# MAX30105_Breakout.net
KiCad netlist of a schematic drawn in EAGLE
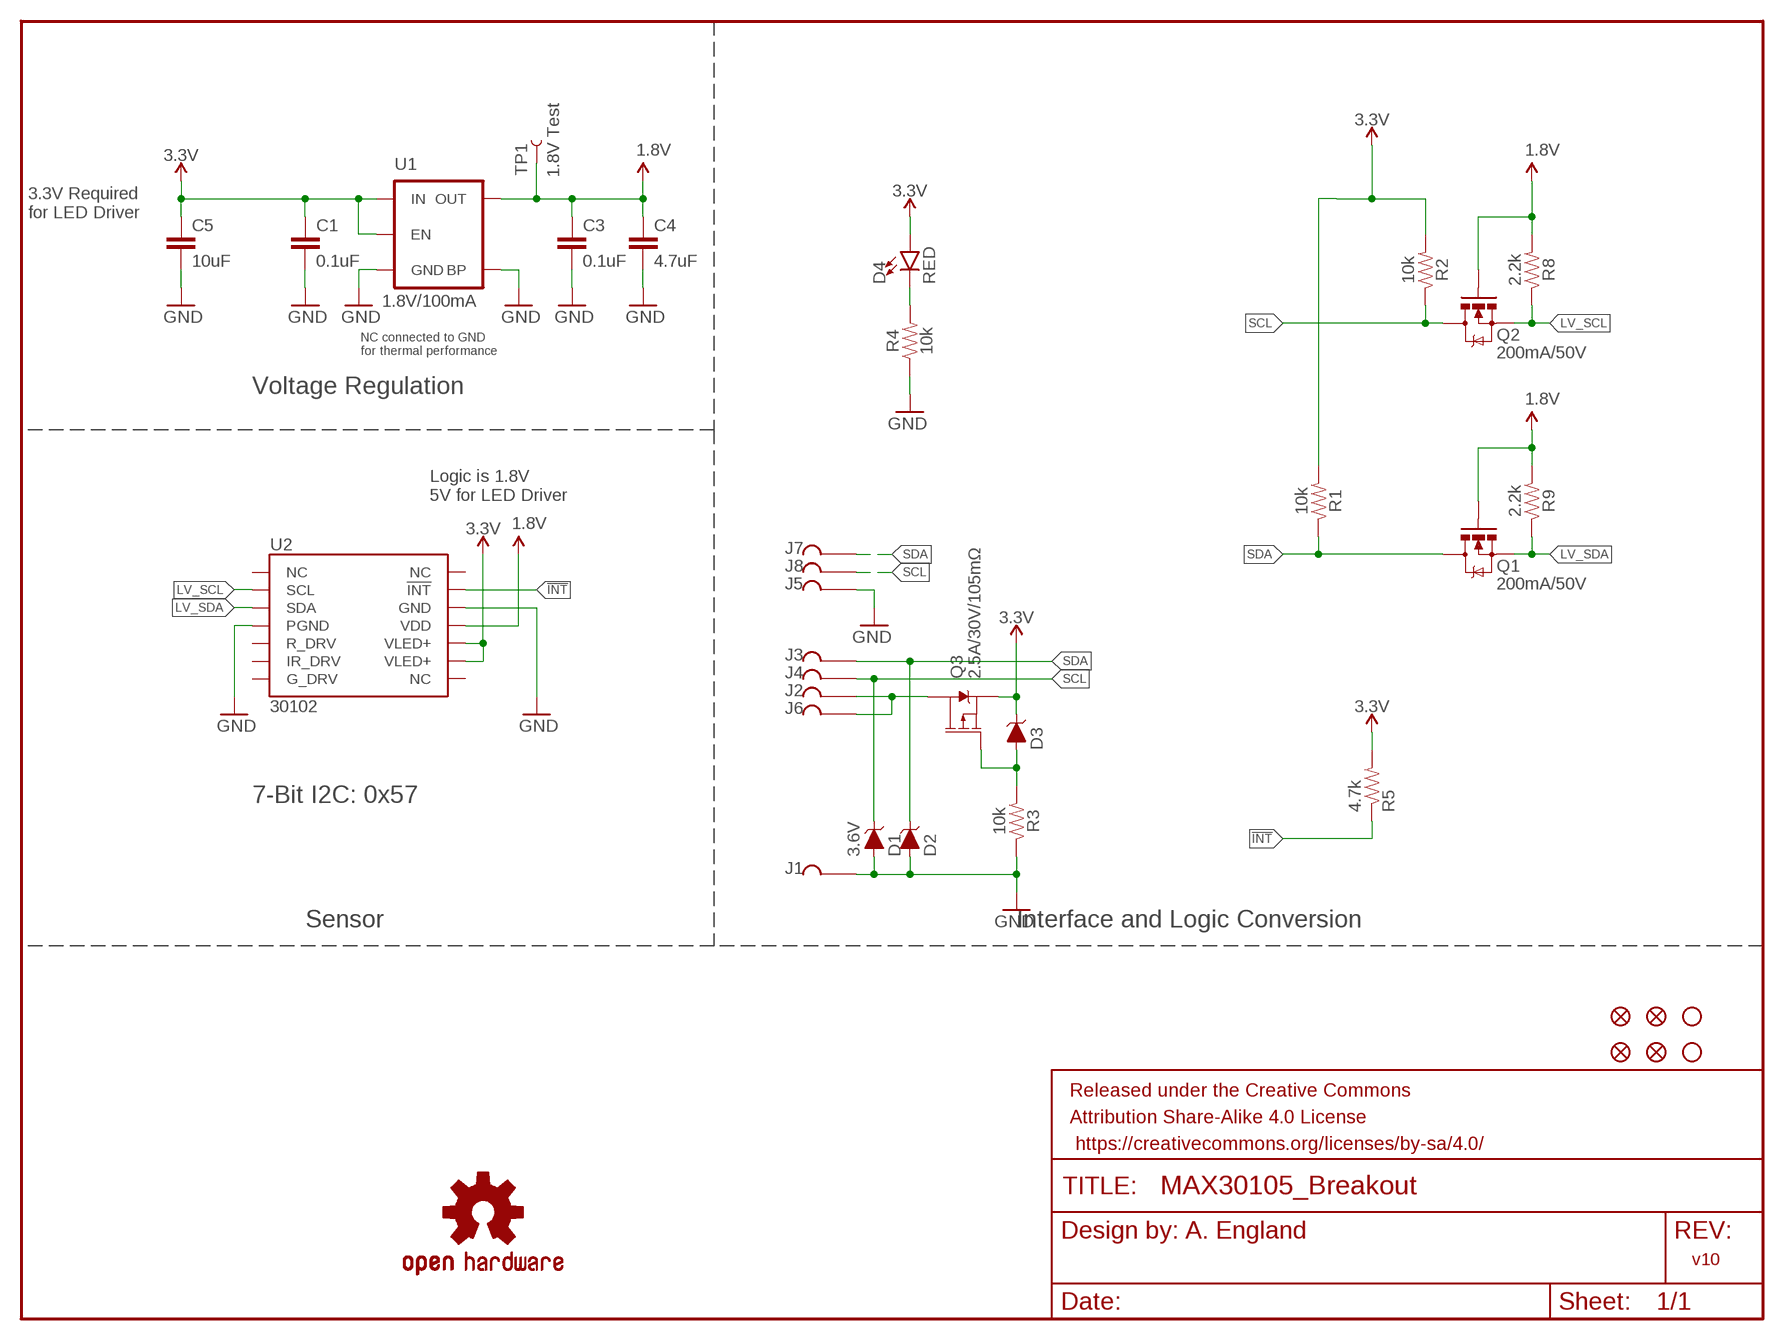
[diagram p0: schematic, sheet 1]

(export (version "E")
  (design (tool "Eeschema 10.0.6"))
  (components
    (comp (ref "C1")
      (value "0.1uF")
      (footprint "eagle-import:0603")
      (libsource (lib "eagle-import") (part "0.1UF-0603-25V-(+80/-20%)"))
    )
    (comp (ref "C3")
      (value "0.1uF")
      (footprint "eagle-import:0603")
      (libsource (lib "eagle-import") (part "0.1UF-0603-25V-(+80/-20%)"))
    )
    (comp (ref "C4")
      (value "4.7uF")
      (footprint "eagle-import:0603")
      (libsource (lib "eagle-import") (part "4.7UF-0603-6.3V-(10%)"))
    )
    (comp (ref "C5")
      (value "10uF")
      (footprint "eagle-import:0603")
      (libsource (lib "eagle-import") (part "10UF-0603-6.3V-20%"))
    )
    (comp (ref "D1")
      (value "3.6V")
      (footprint "eagle-import:SOD-323")
      (libsource (lib "eagle-import") (part "DIODE-ZENER-BZT52C3V6S"))
    )
    (comp (ref "D2")
      (value "3.6V")
      (footprint "eagle-import:SOD-323")
      (libsource (lib "eagle-import") (part "DIODE-ZENER-BZT52C3V6S"))
    )
    (comp (ref "D3")
      (value "3.6V")
      (footprint "eagle-import:SOD-323")
      (libsource (lib "eagle-import") (part "DIODE-ZENER-BZT52C3V6S"))
    )
    (comp (ref "D4")
      (value "RED")
      (footprint "eagle-import:LED-0603")
      (libsource (lib "eagle-import") (part "LED-RED0603"))
    )
    (comp (ref "FID1")
      (value "FIDUCIALUFIDUCIAL")
      (footprint "eagle-import:FIDUCIAL-MICRO")
      (libsource (lib "eagle-import") (part "FIDUCIALUFIDUCIAL"))
    )
    (comp (ref "FID2")
      (value "FIDUCIALUFIDUCIAL")
      (footprint "eagle-import:FIDUCIAL-MICRO")
      (libsource (lib "eagle-import") (part "FIDUCIALUFIDUCIAL"))
    )
    (comp (ref "FID3")
      (value "FIDUCIALUFIDUCIAL")
      (footprint "eagle-import:FIDUCIAL-MICRO")
      (libsource (lib "eagle-import") (part "FIDUCIALUFIDUCIAL"))
    )
    (comp (ref "FID4")
      (value "FIDUCIALUFIDUCIAL")
      (footprint "eagle-import:FIDUCIAL-MICRO")
      (libsource (lib "eagle-import") (part "FIDUCIALUFIDUCIAL"))
    )
    (comp (ref "FRAME1")
      (value "FRAME-LETTER")
      (footprint "eagle-import:CREATIVE_COMMONS")
      (libsource (lib "eagle-import") (part "FRAME-LETTER"))
    )
    (comp (ref "J1")
      (value "GATORGATOR_MINI")
      (footprint "eagle-import:GATOR_MINI")
      (libsource (lib "eagle-import") (part "GATORGATOR_MINI"))
    )
    (comp (ref "J2")
      (value "GATORGATOR_MINI")
      (footprint "eagle-import:GATOR_MINI")
      (libsource (lib "eagle-import") (part "GATORGATOR_MINI"))
    )
    (comp (ref "J3")
      (value "GATORGATOR_MINI")
      (footprint "eagle-import:GATOR_MINI")
      (libsource (lib "eagle-import") (part "GATORGATOR_MINI"))
    )
    (comp (ref "J4")
      (value "GATORGATOR_MINI")
      (footprint "eagle-import:GATOR_MINI")
      (libsource (lib "eagle-import") (part "GATORGATOR_MINI"))
    )
    (comp (ref "J5")
      (value "GATORGATOR_MINI")
      (footprint "eagle-import:GATOR_MINI")
      (libsource (lib "eagle-import") (part "GATORGATOR_MINI"))
    )
    (comp (ref "J6")
      (value "GATORGATOR_MINI")
      (footprint "eagle-import:GATOR_MINI")
      (libsource (lib "eagle-import") (part "GATORGATOR_MINI"))
    )
    (comp (ref "J7")
      (value "GATORGATOR_MINI")
      (footprint "eagle-import:GATOR_MINI")
      (libsource (lib "eagle-import") (part "GATORGATOR_MINI"))
    )
    (comp (ref "J8")
      (value "GATORGATOR_MINI")
      (footprint "eagle-import:GATOR_MINI")
      (libsource (lib "eagle-import") (part "GATORGATOR_MINI"))
    )
    (comp (ref "LOGO2")
      (value "OSHW-LOGOS")
      (footprint "eagle-import:OSHW-LOGO-S")
      (libsource (lib "eagle-import") (part "OSHW-LOGOS"))
    )
    (comp (ref "Q1")
      (value "200mA/50V")
      (footprint "eagle-import:SOT23-3@1")
      (libsource (lib "eagle-import") (part "MOSFET-NCHANNELBSS138"))
    )
    (comp (ref "Q2")
      (value "200mA/50V")
      (footprint "eagle-import:SOT23-3@1")
      (libsource (lib "eagle-import") (part "MOSFET-NCHANNELBSS138"))
    )
    (comp (ref "Q3")
      (value "2.5A/30V/105mΩ")
      (footprint "eagle-import:SOT23-3")
      (libsource (lib "eagle-import") (part "MOSFET_PCH-DMG2307L"))
    )
    (comp (ref "R1")
      (value "10k")
      (footprint "eagle-import:0603")
      (libsource (lib "eagle-import") (part "10KOHM-0603-1/10W-1%"))
    )
    (comp (ref "R2")
      (value "10k")
      (footprint "eagle-import:0603")
      (libsource (lib "eagle-import") (part "10KOHM-0603-1/10W-1%"))
    )
    (comp (ref "R3")
      (value "10k")
      (footprint "eagle-import:0603")
      (libsource (lib "eagle-import") (part "10KOHM-0603-1/10W-1%"))
    )
    (comp (ref "R4")
      (value "10k")
      (footprint "eagle-import:0603")
      (libsource (lib "eagle-import") (part "10KOHM-0603-1/10W-1%"))
    )
    (comp (ref "R5")
      (value "4.7k")
      (footprint "eagle-import:0603")
      (libsource (lib "eagle-import") (part "4.7KOHM-0603-1/10W-1%"))
    )
    (comp (ref "R8")
      (value "2.2k")
      (footprint "eagle-import:0603")
      (libsource (lib "eagle-import") (part "2.2KOHM-0603-1/10W-1%"))
    )
    (comp (ref "R9")
      (value "2.2k")
      (footprint "eagle-import:0603")
      (libsource (lib "eagle-import") (part "2.2KOHM-0603-1/10W-1%"))
    )
    (comp (ref "STANDOFF2")
      (value "STAND-OFF")
      (footprint "eagle-import:STAND-OFF")
      (libsource (lib "eagle-import") (part "STAND-OFF"))
    )
    (comp (ref "STANDOFF3")
      (value "STAND-OFF")
      (footprint "eagle-import:STAND-OFF")
      (libsource (lib "eagle-import") (part "STAND-OFF"))
    )
    (comp (ref "TP1")
      (value "1.8V Test")
      (footprint "eagle-import:PAD.03X.04")
      (libsource (lib "eagle-import") (part "TEST-POINT3X4"))
    )
    (comp (ref "U1")
      (value "1.8V/100mA")
      (footprint "eagle-import:SC70")
      (libsource (lib "eagle-import") (part "V_REG_SP62141.8V"))
    )
    (comp (ref "U2")
      (value "30102")
      (footprint "eagle-import:OLGA-14")
      (libsource (lib "eagle-import") (part "MAX3010X-30102"))
    )
  )
  (nets
    (net (code "1") (name "/~{INT}") (class "Default")
      (node (ref "R5") (pin "1") (pinfunction "1_1") (pintype "passive"))
      (node (ref "U2") (pin "13") (pinfunction "~{INT}_13") (pintype "bidirectional"))
    )
    (net (code "2") (name "1.8V") (class "Default")
      (node (ref "C3") (pin "1") (pinfunction "1_1") (pintype "passive"))
      (node (ref "C4") (pin "1") (pinfunction "1_1") (pintype "passive"))
      (node (ref "Q1") (pin "1") (pinfunction "G_1") (pintype "passive"))
      (node (ref "Q2") (pin "1") (pinfunction "G_1") (pintype "passive"))
      (node (ref "R8") (pin "2") (pinfunction "2_2") (pintype "passive"))
      (node (ref "R9") (pin "2") (pinfunction "2_2") (pintype "passive"))
      (node (ref "TP1") (pin "P$1") (pinfunction "1_P$1") (pintype "bidirectional"))
      (node (ref "U1") (pin "5") (pinfunction "OUT_5") (pintype "passive"))
      (node (ref "U2") (pin "11") (pinfunction "VDD_11") (pintype "bidirectional"))
    )
    (net (code "3") (name "3.3V") (class "Default")
      (node (ref "C1") (pin "1") (pinfunction "1_1") (pintype "passive"))
      (node (ref "C5") (pin "1") (pinfunction "1_1") (pintype "passive"))
      (node (ref "D3") (pin "C") (pinfunction "C_C") (pintype "passive"))
      (node (ref "D4") (pin "A") (pinfunction "A_A") (pintype "passive"))
      (node (ref "Q3") (pin "2") (pinfunction "S_2") (pintype "bidirectional"))
      (node (ref "R1") (pin "2") (pinfunction "2_2") (pintype "passive"))
      (node (ref "R2") (pin "2") (pinfunction "2_2") (pintype "passive"))
      (node (ref "R5") (pin "2") (pinfunction "2_2") (pintype "passive"))
      (node (ref "U1") (pin "1") (pinfunction "IN_1") (pintype "input"))
      (node (ref "U1") (pin "3") (pinfunction "EN_3") (pintype "input"))
      (node (ref "U2") (pin "10") (pinfunction "VLED+_10") (pintype "bidirectional"))
      (node (ref "U2") (pin "9") (pinfunction "VLED+_9") (pintype "bidirectional"))
    )
    (net (code "4") (name "GND") (class "Default")
      (node (ref "C1") (pin "2") (pinfunction "2_2") (pintype "passive"))
      (node (ref "C3") (pin "2") (pinfunction "2_2") (pintype "passive"))
      (node (ref "C4") (pin "2") (pinfunction "2_2") (pintype "passive"))
      (node (ref "C5") (pin "2") (pinfunction "2_2") (pintype "passive"))
      (node (ref "D1") (pin "A") (pinfunction "A_A") (pintype "passive"))
      (node (ref "D2") (pin "A") (pinfunction "A_A") (pintype "passive"))
      (node (ref "J1") (pin "P$2") (pinfunction "P$1_P$2") (pintype "bidirectional"))
      (node (ref "J5") (pin "P$2") (pinfunction "P$1_P$2") (pintype "bidirectional"))
      (node (ref "R3") (pin "1") (pinfunction "1_1") (pintype "passive"))
      (node (ref "R4") (pin "1") (pinfunction "1_1") (pintype "passive"))
      (node (ref "U1") (pin "2") (pinfunction "GND_2") (pintype "input"))
      (node (ref "U1") (pin "4") (pinfunction "BP_4") (pintype "input"))
      (node (ref "U2") (pin "12") (pinfunction "GND_12") (pintype "bidirectional"))
      (node (ref "U2") (pin "4") (pinfunction "PGND_4") (pintype "bidirectional"))
    )
    (net (code "5") (name "LV_SCL") (class "Default")
      (node (ref "Q2") (pin "2") (pinfunction "S_2") (pintype "passive"))
      (node (ref "R8") (pin "1") (pinfunction "1_1") (pintype "passive"))
      (node (ref "U2") (pin "2") (pinfunction "SCL_2") (pintype "bidirectional"))
    )
    (net (code "6") (name "LV_SDA") (class "Default")
      (node (ref "Q1") (pin "2") (pinfunction "S_2") (pintype "passive"))
      (node (ref "R9") (pin "1") (pinfunction "1_1") (pintype "passive"))
      (node (ref "U2") (pin "3") (pinfunction "SDA_3") (pintype "bidirectional"))
    )
    (net (code "7") (name "Net-(D4-PadC)") (class "Default")
      (node (ref "D4") (pin "C") (pinfunction "C_C") (pintype "passive"))
      (node (ref "R4") (pin "2") (pinfunction "2_2") (pintype "passive"))
    )
    (net (code "8") (name "Net-(J2-P$1)") (class "Default")
      (node (ref "J2") (pin "P$2") (pinfunction "P$1_P$2") (pintype "bidirectional"))
      (node (ref "J6") (pin "P$2") (pinfunction "P$1_P$2") (pintype "bidirectional"))
      (node (ref "Q3") (pin "3") (pinfunction "D_3") (pintype "bidirectional"))
    )
    (net (code "9") (name "Net-(Q3-G)") (class "Default")
      (node (ref "D3") (pin "A") (pinfunction "A_A") (pintype "passive"))
      (node (ref "Q3") (pin "1") (pinfunction "G_1") (pintype "bidirectional"))
      (node (ref "R3") (pin "2") (pinfunction "2_2") (pintype "passive"))
    )
    (net (code "10") (name "SCL") (class "Default")
      (node (ref "D1") (pin "C") (pinfunction "C_C") (pintype "passive"))
      (node (ref "J4") (pin "P$2") (pinfunction "P$1_P$2") (pintype "bidirectional"))
      (node (ref "J8") (pin "P$2") (pinfunction "P$1_P$2") (pintype "bidirectional"))
      (node (ref "Q2") (pin "3") (pinfunction "D_3") (pintype "passive"))
      (node (ref "R2") (pin "1") (pinfunction "1_1") (pintype "passive"))
    )
    (net (code "11") (name "SDA") (class "Default")
      (node (ref "D2") (pin "C") (pinfunction "C_C") (pintype "passive"))
      (node (ref "J3") (pin "P$2") (pinfunction "P$1_P$2") (pintype "bidirectional"))
      (node (ref "J7") (pin "P$2") (pinfunction "P$1_P$2") (pintype "bidirectional"))
      (node (ref "Q1") (pin "3") (pinfunction "D_3") (pintype "passive"))
      (node (ref "R1") (pin "1") (pinfunction "1_1") (pintype "passive"))
    )
    (net (code "12") (name "unconnected-(U2-G_DRV-Pad7)") (class "Default")
      (node (ref "U2") (pin "7") (pinfunction "G_DRV_7") (pintype "bidirectional"))
    )
    (net (code "13") (name "unconnected-(U2-IR_DRV-Pad6)") (class "Default")
      (node (ref "U2") (pin "6") (pinfunction "IR_DRV_6") (pintype "bidirectional"))
    )
    (net (code "14") (name "unconnected-(U2-NC-Pad1)") (class "Default")
      (node (ref "U2") (pin "1") (pinfunction "NC_1") (pintype "bidirectional"))
    )
    (net (code "15") (name "unconnected-(U2-NC-Pad8)") (class "Default")
      (node (ref "U2") (pin "8") (pinfunction "NC_8") (pintype "bidirectional"))
    )
    (net (code "16") (name "unconnected-(U2-NC-Pad14)") (class "Default")
      (node (ref "U2") (pin "14") (pinfunction "NC_14") (pintype "bidirectional"))
    )
    (net (code "17") (name "unconnected-(U2-R_DRV-Pad5)") (class "Default")
      (node (ref "U2") (pin "5") (pinfunction "R_DRV_5") (pintype "bidirectional"))
    )
  )
)
